# SensorBoard_01.net
KiCad netlist of a schematic drawn in EAGLE
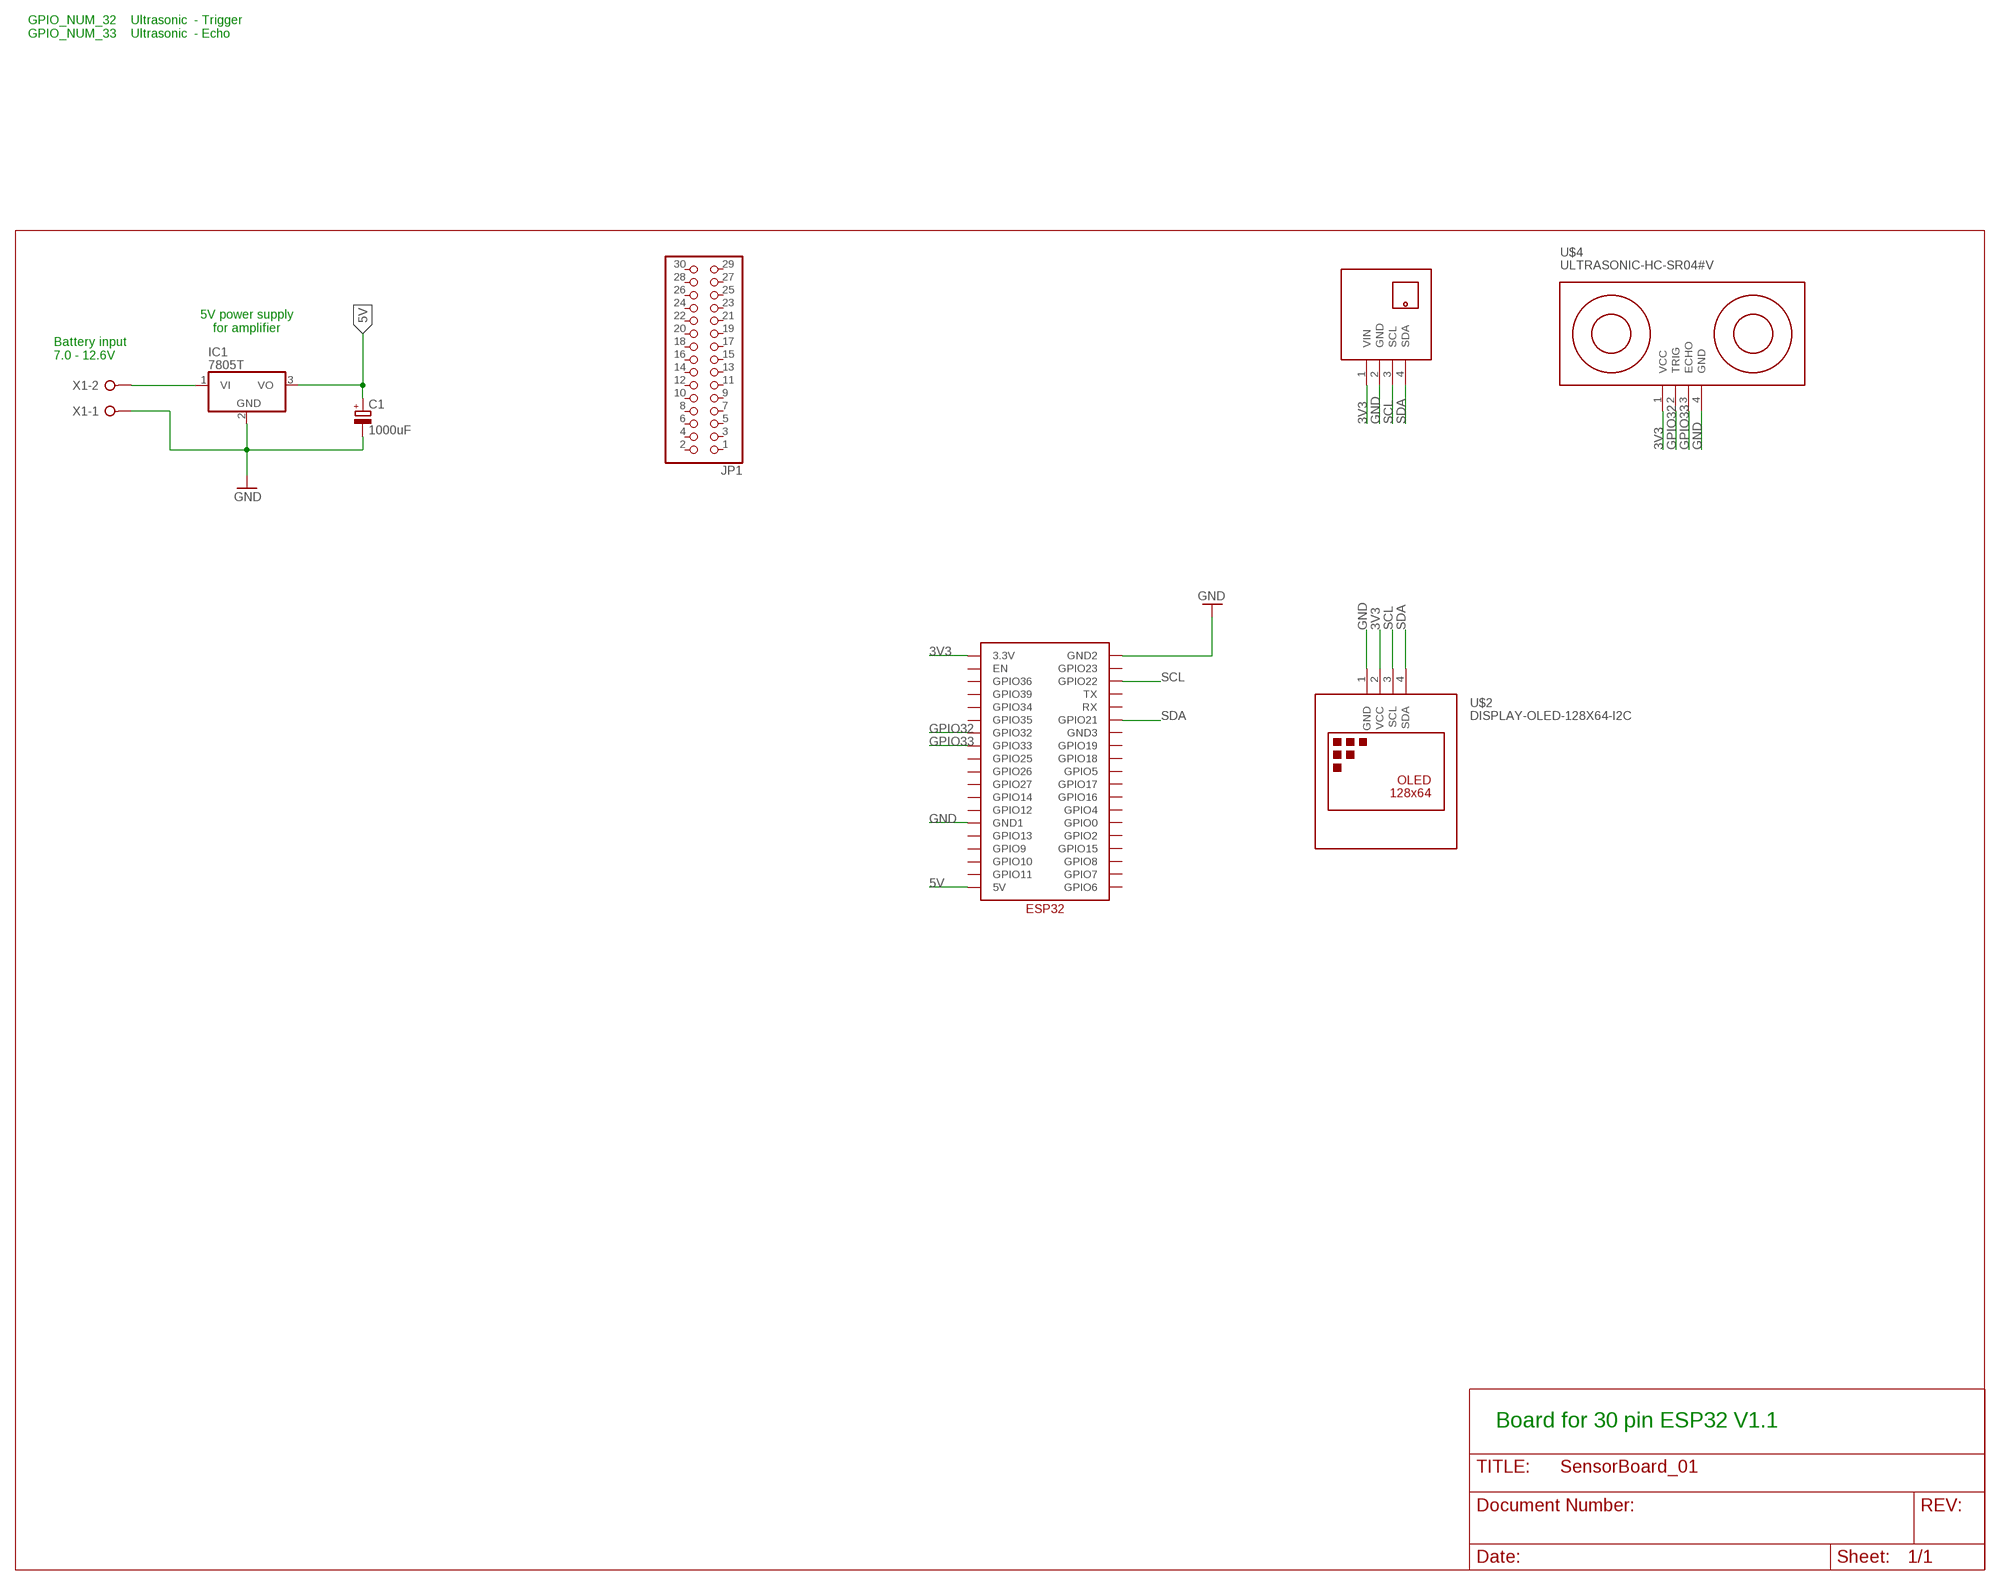
[diagram p0: schematic, sheet 1]

(export (version "E")
  (design (tool "Eeschema 10.0.6"))
  (components
    (comp (ref "C1")
      (value "1000uF")
      (footprint "eagle-import:E5-10,5")
      (libsource (lib "eagle-import") (part "CPOL-EUE5-10.5"))
    )
    (comp (ref "IC1")
      (value "7805T")
      (footprint "eagle-import:TO220H")
      (libsource (lib "eagle-import") (part "78T05"))
    )
    (comp (ref "JP1")
      (value "PINHD-2X15")
      (footprint "eagle-import:2X15")
      (libsource (lib "eagle-import") (part "PINHD-2X15"))
    )
    (comp (ref "U$1")
      (value "ESP32")
      (footprint "eagle-import:ESP32")
      (libsource (lib "eagle-import") (part "ESP32"))
    )
    (comp (ref "U$2")
      (value "DISPLAY-OLED-128X64-I2C")
      (footprint "eagle-import:DISPLAY-OLED-128X64-I2C")
      (libsource (lib "eagle-import") (part "DISPLAY-OLED-128X64-I2C"))
    )
    (comp (ref "U$3")
      (value "TEMP-HUM-PRES-BME280")
      (footprint "eagle-import:TEMP-HUM-PRES-BME280")
      (libsource (lib "eagle-import") (part "TEMP-HUM-PRES-BME280"))
    )
    (comp (ref "U$4")
      (value "ULTRASONIC-HC-SR04#V")
      (footprint "eagle-import:ULTRASONIC-HC-SR04#V")
      (libsource (lib "eagle-import") (part "ULTRASONIC-HC-SR04#V"))
    )
    (comp (ref "X1")
      (value "W237-02P")
      (footprint "eagle-import:W237-132")
      (libsource (lib "eagle-import") (part "W237-02P"))
    )
  )
  (nets
    (net (code "1") (name "/3V3") (class "Default")
      (node (ref "U$1") (pin "3.3V") (pinfunction "3.3V_3.3V") (pintype "bidirectional"))
      (node (ref "U$2") (pin "2") (pinfunction "VCC_2") (pintype "power_in"))
      (node (ref "U$3") (pin "1") (pinfunction "VIN_1") (pintype "power_in"))
      (node (ref "U$4") (pin "1") (pinfunction "VCC_1") (pintype "power_in"))
    )
    (net (code "2") (name "/GPIO32") (class "Default")
      (node (ref "U$1") (pin "GPIO32") (pinfunction "GPIO32_GPIO32") (pintype "bidirectional"))
      (node (ref "U$4") (pin "2") (pinfunction "TRIG_2") (pintype "input"))
    )
    (net (code "3") (name "/GPIO33") (class "Default")
      (node (ref "U$1") (pin "GPIO33") (pinfunction "GPIO33_GPIO33") (pintype "bidirectional"))
      (node (ref "U$4") (pin "3") (pinfunction "ECHO_3") (pintype "output"))
    )
    (net (code "4") (name "/SCL") (class "Default")
      (node (ref "U$1") (pin "GPIO22") (pinfunction "GPIO22_GPIO22") (pintype "bidirectional"))
      (node (ref "U$2") (pin "3") (pinfunction "SCL_3") (pintype "bidirectional"))
      (node (ref "U$3") (pin "3") (pinfunction "SCL_3") (pintype "bidirectional"))
    )
    (net (code "5") (name "/SDA") (class "Default")
      (node (ref "U$1") (pin "GPIO21") (pinfunction "GPIO21_GPIO21") (pintype "bidirectional"))
      (node (ref "U$2") (pin "4") (pinfunction "SDA_4") (pintype "bidirectional"))
      (node (ref "U$3") (pin "4") (pinfunction "SDA_4") (pintype "bidirectional"))
    )
    (net (code "6") (name "5V") (class "Default")
      (node (ref "C1") (pin "+") (pinfunction "+_+") (pintype "passive"))
      (node (ref "IC1") (pin "3") (pinfunction "VO_3") (pintype "passive"))
      (node (ref "U$1") (pin "5V") (pinfunction "5V_5V") (pintype "bidirectional"))
    )
    (net (code "7") (name "GND") (class "Default")
      (node (ref "C1") (pin "-") (pinfunction "-_-") (pintype "passive"))
      (node (ref "IC1") (pin "2") (pinfunction "GND_2") (pintype "passive"))
      (node (ref "U$1") (pin "GND1") (pinfunction "GND1_GND1") (pintype "bidirectional"))
      (node (ref "U$1") (pin "GND2") (pinfunction "GND2_GND2") (pintype "bidirectional"))
      (node (ref "U$2") (pin "1") (pinfunction "GND_1") (pintype "power_in"))
      (node (ref "U$3") (pin "2") (pinfunction "GND_2") (pintype "power_in"))
      (node (ref "U$4") (pin "4") (pinfunction "GND_4") (pintype "power_in"))
      (node (ref "X1") (pin "1") (pinfunction "KL_1") (pintype "passive"))
    )
    (net (code "8") (name "Net-(IC1-VI)") (class "Default")
      (node (ref "IC1") (pin "1") (pinfunction "VI_1") (pintype "input"))
      (node (ref "X1") (pin "2") (pinfunction "KL_2") (pintype "passive"))
    )
    (net (code "9") (name "unconnected-(JP1-Pad1)") (class "Default")
      (node (ref "JP1") (pin "1") (pinfunction "1_1") (pintype "passive"))
    )
    (net (code "10") (name "unconnected-(JP1-Pad2)") (class "Default")
      (node (ref "JP1") (pin "2") (pinfunction "2_2") (pintype "passive"))
    )
    (net (code "11") (name "unconnected-(JP1-Pad3)") (class "Default")
      (node (ref "JP1") (pin "3") (pinfunction "3_3") (pintype "passive"))
    )
    (net (code "12") (name "unconnected-(JP1-Pad4)") (class "Default")
      (node (ref "JP1") (pin "4") (pinfunction "4_4") (pintype "passive"))
    )
    (net (code "13") (name "unconnected-(JP1-Pad5)") (class "Default")
      (node (ref "JP1") (pin "5") (pinfunction "5_5") (pintype "passive"))
    )
    (net (code "14") (name "unconnected-(JP1-Pad6)") (class "Default")
      (node (ref "JP1") (pin "6") (pinfunction "6_6") (pintype "passive"))
    )
    (net (code "15") (name "unconnected-(JP1-Pad7)") (class "Default")
      (node (ref "JP1") (pin "7") (pinfunction "7_7") (pintype "passive"))
    )
    (net (code "16") (name "unconnected-(JP1-Pad8)") (class "Default")
      (node (ref "JP1") (pin "8") (pinfunction "8_8") (pintype "passive"))
    )
    (net (code "17") (name "unconnected-(JP1-Pad9)") (class "Default")
      (node (ref "JP1") (pin "9") (pinfunction "9_9") (pintype "passive"))
    )
    (net (code "18") (name "unconnected-(JP1-Pad10)") (class "Default")
      (node (ref "JP1") (pin "10") (pinfunction "10_10") (pintype "passive"))
    )
    (net (code "19") (name "unconnected-(JP1-Pad11)") (class "Default")
      (node (ref "JP1") (pin "11") (pinfunction "11_11") (pintype "passive"))
    )
    (net (code "20") (name "unconnected-(JP1-Pad12)") (class "Default")
      (node (ref "JP1") (pin "12") (pinfunction "12_12") (pintype "passive"))
    )
    (net (code "21") (name "unconnected-(JP1-Pad13)") (class "Default")
      (node (ref "JP1") (pin "13") (pinfunction "13_13") (pintype "passive"))
    )
    (net (code "22") (name "unconnected-(JP1-Pad14)") (class "Default")
      (node (ref "JP1") (pin "14") (pinfunction "14_14") (pintype "passive"))
    )
    (net (code "23") (name "unconnected-(JP1-Pad15)") (class "Default")
      (node (ref "JP1") (pin "15") (pinfunction "15_15") (pintype "passive"))
    )
    (net (code "24") (name "unconnected-(JP1-Pad16)") (class "Default")
      (node (ref "JP1") (pin "16") (pinfunction "16_16") (pintype "passive"))
    )
    (net (code "25") (name "unconnected-(JP1-Pad17)") (class "Default")
      (node (ref "JP1") (pin "17") (pinfunction "17_17") (pintype "passive"))
    )
    (net (code "26") (name "unconnected-(JP1-Pad18)") (class "Default")
      (node (ref "JP1") (pin "18") (pinfunction "18_18") (pintype "passive"))
    )
    (net (code "27") (name "unconnected-(JP1-Pad19)") (class "Default")
      (node (ref "JP1") (pin "19") (pinfunction "19_19") (pintype "passive"))
    )
    (net (code "28") (name "unconnected-(JP1-Pad20)") (class "Default")
      (node (ref "JP1") (pin "20") (pinfunction "20_20") (pintype "passive"))
    )
    (net (code "29") (name "unconnected-(JP1-Pad21)") (class "Default")
      (node (ref "JP1") (pin "21") (pinfunction "21_21") (pintype "passive"))
    )
    (net (code "30") (name "unconnected-(JP1-Pad22)") (class "Default")
      (node (ref "JP1") (pin "22") (pinfunction "22_22") (pintype "passive"))
    )
    (net (code "31") (name "unconnected-(JP1-Pad23)") (class "Default")
      (node (ref "JP1") (pin "23") (pinfunction "23_23") (pintype "passive"))
    )
    (net (code "32") (name "unconnected-(JP1-Pad24)") (class "Default")
      (node (ref "JP1") (pin "24") (pinfunction "24_24") (pintype "passive"))
    )
    (net (code "33") (name "unconnected-(JP1-Pad25)") (class "Default")
      (node (ref "JP1") (pin "25") (pinfunction "25_25") (pintype "passive"))
    )
    (net (code "34") (name "unconnected-(JP1-Pad26)") (class "Default")
      (node (ref "JP1") (pin "26") (pinfunction "26_26") (pintype "passive"))
    )
    (net (code "35") (name "unconnected-(JP1-Pad27)") (class "Default")
      (node (ref "JP1") (pin "27") (pinfunction "27_27") (pintype "passive"))
    )
    (net (code "36") (name "unconnected-(JP1-Pad28)") (class "Default")
      (node (ref "JP1") (pin "28") (pinfunction "28_28") (pintype "passive"))
    )
    (net (code "37") (name "unconnected-(JP1-Pad29)") (class "Default")
      (node (ref "JP1") (pin "29") (pinfunction "29_29") (pintype "passive"))
    )
    (net (code "38") (name "unconnected-(JP1-Pad30)") (class "Default")
      (node (ref "JP1") (pin "30") (pinfunction "30_30") (pintype "passive"))
    )
    (net (code "39") (name "unconnected-(U$1-PadEN)") (class "Default")
      (node (ref "U$1") (pin "EN") (pinfunction "EN_EN") (pintype "bidirectional"))
    )
    (net (code "40") (name "unconnected-(U$1-PadGND3)") (class "Default")
      (node (ref "U$1") (pin "GND3") (pinfunction "GND3_GND3") (pintype "bidirectional"))
    )
    (net (code "41") (name "unconnected-(U$1-PadGPIO0)") (class "Default")
      (node (ref "U$1") (pin "GPIO0") (pinfunction "GPIO0_GPIO0") (pintype "bidirectional"))
    )
    (net (code "42") (name "unconnected-(U$1-PadGPIO2)") (class "Default")
      (node (ref "U$1") (pin "GPIO2") (pinfunction "GPIO2_GPIO2") (pintype "bidirectional"))
    )
    (net (code "43") (name "unconnected-(U$1-PadGPIO4)") (class "Default")
      (node (ref "U$1") (pin "GPIO4") (pinfunction "GPIO4_GPIO4") (pintype "bidirectional"))
    )
    (net (code "44") (name "unconnected-(U$1-PadGPIO5)") (class "Default")
      (node (ref "U$1") (pin "GPIO5") (pinfunction "GPIO5_GPIO5") (pintype "bidirectional"))
    )
    (net (code "45") (name "unconnected-(U$1-PadGPIO6)") (class "Default")
      (node (ref "U$1") (pin "GPIO6") (pinfunction "GPIO6_GPIO6") (pintype "bidirectional"))
    )
    (net (code "46") (name "unconnected-(U$1-PadGPIO7)") (class "Default")
      (node (ref "U$1") (pin "GPIO7") (pinfunction "GPIO7_GPIO7") (pintype "bidirectional"))
    )
    (net (code "47") (name "unconnected-(U$1-PadGPIO8)") (class "Default")
      (node (ref "U$1") (pin "GPIO8") (pinfunction "GPIO8_GPIO8") (pintype "bidirectional"))
    )
    (net (code "48") (name "unconnected-(U$1-PadGPIO9)") (class "Default")
      (node (ref "U$1") (pin "GPIO9") (pinfunction "GPIO9_GPIO9") (pintype "bidirectional"))
    )
    (net (code "49") (name "unconnected-(U$1-PadGPIO10)") (class "Default")
      (node (ref "U$1") (pin "GPIO10") (pinfunction "GPIO10_GPIO10") (pintype "bidirectional"))
    )
    (net (code "50") (name "unconnected-(U$1-PadGPIO11)") (class "Default")
      (node (ref "U$1") (pin "GPIO11") (pinfunction "GPIO11_GPIO11") (pintype "bidirectional"))
    )
    (net (code "51") (name "unconnected-(U$1-PadGPIO12)") (class "Default")
      (node (ref "U$1") (pin "GPIO12") (pinfunction "GPIO12_GPIO12") (pintype "bidirectional"))
    )
    (net (code "52") (name "unconnected-(U$1-PadGPIO13)") (class "Default")
      (node (ref "U$1") (pin "GPIO13") (pinfunction "GPIO13_GPIO13") (pintype "bidirectional"))
    )
    (net (code "53") (name "unconnected-(U$1-PadGPIO14)") (class "Default")
      (node (ref "U$1") (pin "GPIO14") (pinfunction "GPIO14_GPIO14") (pintype "bidirectional"))
    )
    (net (code "54") (name "unconnected-(U$1-PadGPIO15)") (class "Default")
      (node (ref "U$1") (pin "GPIO15") (pinfunction "GPIO15_GPIO15") (pintype "bidirectional"))
    )
    (net (code "55") (name "unconnected-(U$1-PadGPIO16)") (class "Default")
      (node (ref "U$1") (pin "GPIO16") (pinfunction "GPIO16_GPIO16") (pintype "bidirectional"))
    )
    (net (code "56") (name "unconnected-(U$1-PadGPIO17)") (class "Default")
      (node (ref "U$1") (pin "GPIO17") (pinfunction "GPIO17_GPIO17") (pintype "bidirectional"))
    )
    (net (code "57") (name "unconnected-(U$1-PadGPIO18)") (class "Default")
      (node (ref "U$1") (pin "GPIO18") (pinfunction "GPIO18_GPIO18") (pintype "bidirectional"))
    )
    (net (code "58") (name "unconnected-(U$1-PadGPIO19)") (class "Default")
      (node (ref "U$1") (pin "GPIO19") (pinfunction "GPIO19_GPIO19") (pintype "bidirectional"))
    )
    (net (code "59") (name "unconnected-(U$1-PadGPIO23)") (class "Default")
      (node (ref "U$1") (pin "GPIO23") (pinfunction "GPIO23_GPIO23") (pintype "bidirectional"))
    )
    (net (code "60") (name "unconnected-(U$1-PadGPIO25)") (class "Default")
      (node (ref "U$1") (pin "GPIO25") (pinfunction "GPIO25_GPIO25") (pintype "bidirectional"))
    )
    (net (code "61") (name "unconnected-(U$1-PadGPIO26)") (class "Default")
      (node (ref "U$1") (pin "GPIO26") (pinfunction "GPIO26_GPIO26") (pintype "bidirectional"))
    )
    (net (code "62") (name "unconnected-(U$1-PadGPIO27)") (class "Default")
      (node (ref "U$1") (pin "GPIO27") (pinfunction "GPIO27_GPIO27") (pintype "bidirectional"))
    )
    (net (code "63") (name "unconnected-(U$1-PadGPIO34)") (class "Default")
      (node (ref "U$1") (pin "GPIO34") (pinfunction "GPIO34_GPIO34") (pintype "bidirectional"))
    )
    (net (code "64") (name "unconnected-(U$1-PadGPIO35)") (class "Default")
      (node (ref "U$1") (pin "GPIO35") (pinfunction "GPIO35_GPIO35") (pintype "bidirectional"))
    )
    (net (code "65") (name "unconnected-(U$1-PadGPIO36)") (class "Default")
      (node (ref "U$1") (pin "GPIO36") (pinfunction "GPIO36_GPIO36") (pintype "bidirectional"))
    )
    (net (code "66") (name "unconnected-(U$1-PadGPIO39)") (class "Default")
      (node (ref "U$1") (pin "GPIO39") (pinfunction "GPIO39_GPIO39") (pintype "bidirectional"))
    )
    (net (code "67") (name "unconnected-(U$1-PadRX)") (class "Default")
      (node (ref "U$1") (pin "RX") (pinfunction "RX_RX") (pintype "bidirectional"))
    )
    (net (code "68") (name "unconnected-(U$1-PadTX)") (class "Default")
      (node (ref "U$1") (pin "TX") (pinfunction "TX_TX") (pintype "bidirectional"))
    )
  )
)
